# STM32_LineFlow.net
KiCad netlist of a schematic drawn in Altium Designer
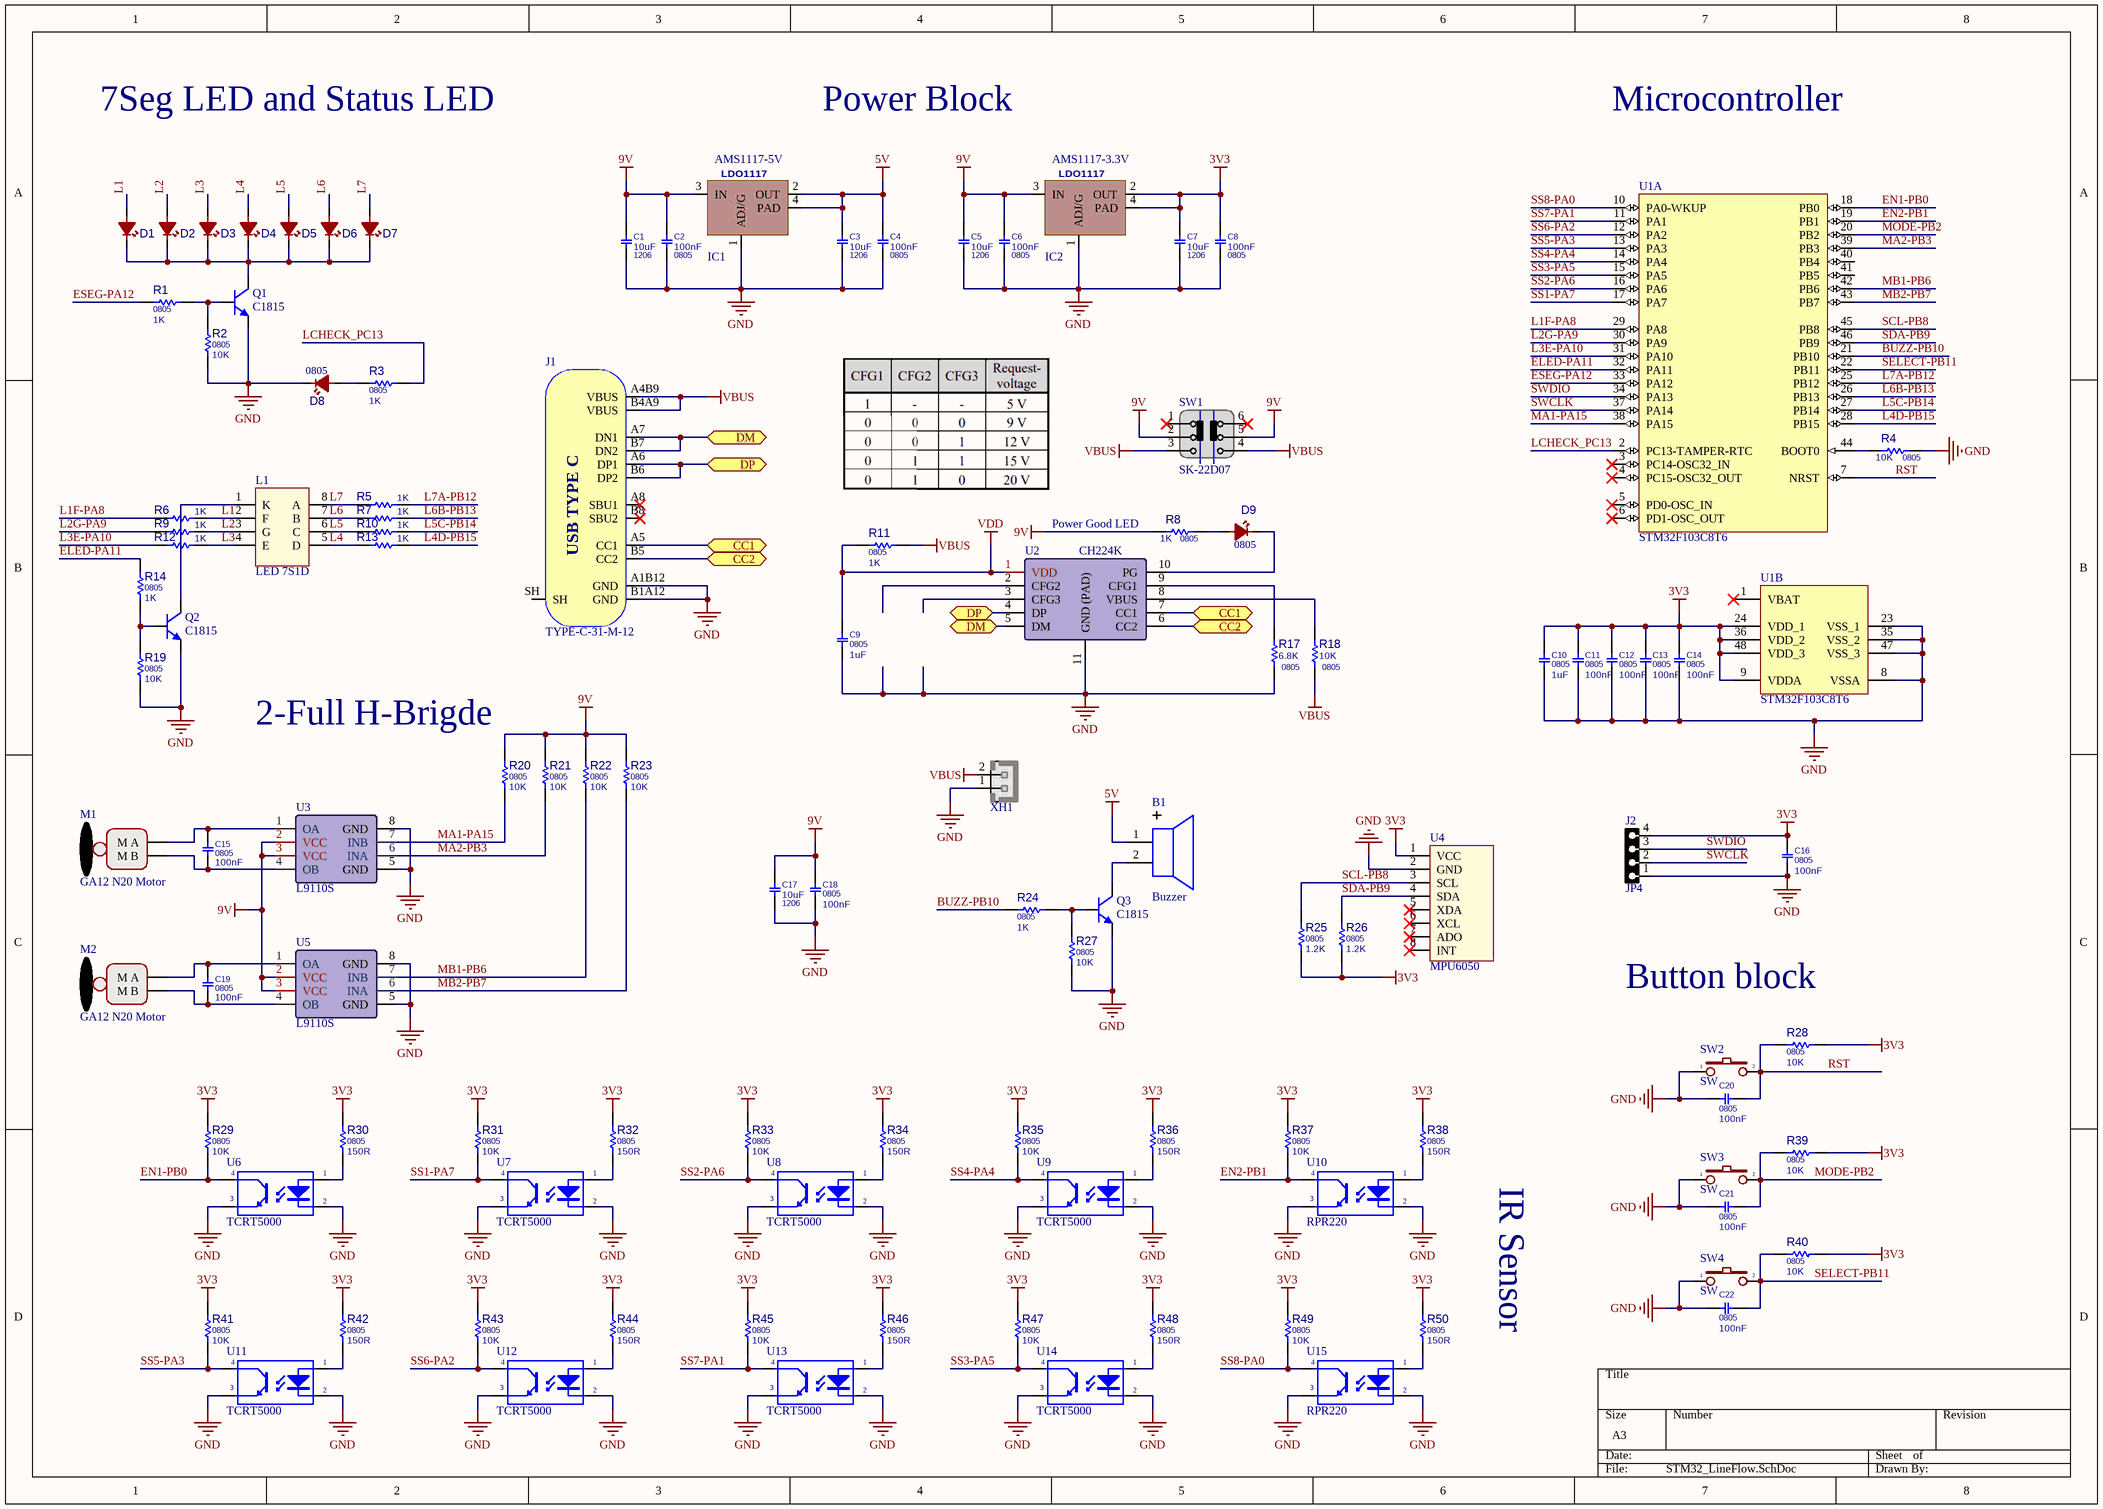
[diagram p0: STM32_LineFlow.SchDoc]

(export (version "E")
  (design (tool "Eeschema 10.0.6"))
  (components
    (comp (ref "B1") (value "Buzzer") (footprint "Buzzer") (libsource (lib "IoT - Copy") (part "Buzzer")))
    (comp (ref "C1")
      (value "1206")
      (footprint "cap_1206")
      (description "CAP SMD")
      (fields (field (name "MANF_P#") "MANF_PART#") (field (name "ALTIUM_VALUE") "10uF"))
      (libsource (lib "IoT") (part "CAP SMD"))
    )
    (comp (ref "C2")
      (value "0805")
      (footprint "cap_0805")
      (description "CAP SMD")
      (fields (field (name "MANF_P#") "MANF_PART#") (field (name "ALTIUM_VALUE") "100nF"))
      (libsource (lib "IoT") (part "CAP SMD"))
    )
    (comp (ref "C3")
      (value "1206")
      (footprint "cap_1206")
      (description "CAP SMD")
      (fields (field (name "MANF_P#") "MANF_PART#") (field (name "ALTIUM_VALUE") "10uF"))
      (libsource (lib "IoT") (part "CAP SMD"))
    )
    (comp (ref "C4")
      (value "0805")
      (footprint "cap_0805")
      (description "CAP SMD")
      (fields (field (name "MANF_P#") "MANF_PART#") (field (name "ALTIUM_VALUE") "100nF"))
      (libsource (lib "IoT") (part "CAP SMD"))
    )
    (comp (ref "C5")
      (value "1206")
      (footprint "cap_1206")
      (description "CAP SMD")
      (fields (field (name "MANF_P#") "MANF_PART#") (field (name "ALTIUM_VALUE") "10uF"))
      (libsource (lib "IoT") (part "CAP SMD"))
    )
    (comp (ref "C6")
      (value "0805")
      (footprint "cap_0805")
      (description "CAP SMD")
      (fields (field (name "MANF_P#") "MANF_PART#") (field (name "ALTIUM_VALUE") "100nF"))
      (libsource (lib "IoT") (part "CAP SMD"))
    )
    (comp (ref "C7")
      (value "1206")
      (footprint "cap_1206")
      (description "CAP SMD")
      (fields (field (name "MANF_P#") "MANF_PART#") (field (name "ALTIUM_VALUE") "10uF"))
      (libsource (lib "IoT") (part "CAP SMD"))
    )
    (comp (ref "C8")
      (value "0805")
      (footprint "cap_0805")
      (description "CAP SMD")
      (fields (field (name "MANF_P#") "MANF_PART#") (field (name "ALTIUM_VALUE") "100nF"))
      (libsource (lib "IoT") (part "CAP SMD"))
    )
    (comp (ref "C9")
      (value "0805")
      (footprint "cap_0805")
      (description "CAP SMD")
      (fields (field (name "MANF_P#") "MANF_PART#") (field (name "ALTIUM_VALUE") "1uF"))
      (libsource (lib "IoT - Copy") (part "CAP SMD"))
    )
    (comp (ref "C10")
      (value "0805")
      (footprint "cap_0805")
      (description "CAP SMD")
      (fields (field (name "MANF_P#") "MANF_PART#") (field (name "ALTIUM_VALUE") "1uF"))
      (libsource (lib "IoT - Copy") (part "CAP SMD"))
    )
    (comp (ref "C11")
      (value "0805")
      (footprint "cap_0805")
      (description "CAP SMD")
      (fields (field (name "MANF_P#") "MANF_PART#") (field (name "ALTIUM_VALUE") "100nF"))
      (libsource (lib "IoT - Copy") (part "CAP SMD"))
    )
    (comp (ref "C12")
      (value "0805")
      (footprint "cap_0805")
      (description "CAP SMD")
      (fields (field (name "MANF_P#") "MANF_PART#") (field (name "ALTIUM_VALUE") "100nF"))
      (libsource (lib "IoT - Copy") (part "CAP SMD"))
    )
    (comp (ref "C13")
      (value "0805")
      (footprint "cap_0805")
      (description "CAP SMD")
      (fields (field (name "MANF_P#") "MANF_PART#") (field (name "ALTIUM_VALUE") "100nF"))
      (libsource (lib "IoT - Copy") (part "CAP SMD"))
    )
    (comp (ref "C14")
      (value "0805")
      (footprint "cap_0805")
      (description "CAP SMD")
      (fields (field (name "MANF_P#") "MANF_PART#") (field (name "ALTIUM_VALUE") "100nF"))
      (libsource (lib "IoT - Copy") (part "CAP SMD"))
    )
    (comp (ref "C15")
      (value "0805")
      (footprint "cap_0805")
      (description "CAP SMD")
      (fields (field (name "MANF_P#") "MANF_PART#") (field (name "ALTIUM_VALUE") "100nF"))
      (libsource (lib "IoT - Copy") (part "CAP SMD"))
    )
    (comp (ref "C16")
      (value "0805")
      (footprint "cap_0805")
      (description "CAP SMD")
      (fields (field (name "MANF_P#") "MANF_PART#") (field (name "ALTIUM_VALUE") "100nF"))
      (libsource (lib "IoT - Copy") (part "CAP SMD"))
    )
    (comp (ref "C17")
      (value "1206")
      (footprint "cap_1206")
      (description "CAP SMD")
      (fields (field (name "MANF_P#") "MANF_PART#") (field (name "ALTIUM_VALUE") "10uF"))
      (libsource (lib "IoT") (part "CAP SMD"))
    )
    (comp (ref "C18")
      (value "0805")
      (footprint "cap_0805")
      (description "CAP SMD")
      (fields (field (name "MANF_P#") "MANF_PART#") (field (name "ALTIUM_VALUE") "100nF"))
      (libsource (lib "IoT - Copy") (part "CAP SMD"))
    )
    (comp (ref "C19")
      (value "0805")
      (footprint "cap_0805")
      (description "CAP SMD")
      (fields (field (name "MANF_P#") "MANF_PART#") (field (name "ALTIUM_VALUE") "100nF"))
      (libsource (lib "IoT - Copy") (part "CAP SMD"))
    )
    (comp (ref "C20")
      (value "0805")
      (footprint "cap_0805")
      (description "CAP SMD")
      (fields (field (name "MANF_P#") "MANF_PART#") (field (name "ALTIUM_VALUE") "100nF"))
      (libsource (lib "IoT - Copy") (part "CAP SMD"))
    )
    (comp (ref "C21")
      (value "0805")
      (footprint "cap_0805")
      (description "CAP SMD")
      (fields (field (name "MANF_P#") "MANF_PART#") (field (name "ALTIUM_VALUE") "100nF"))
      (libsource (lib "IoT - Copy") (part "CAP SMD"))
    )
    (comp (ref "C22")
      (value "0805")
      (footprint "cap_0805")
      (description "CAP SMD")
      (fields (field (name "MANF_P#") "MANF_PART#") (field (name "ALTIUM_VALUE") "100nF"))
      (libsource (lib "IoT - Copy") (part "CAP SMD"))
    )
    (comp (ref "D1")
      (value "0805")
      (footprint "LED0805RED")
      (description "LED Red SMD")
      (fields (field (name "MANF") "MANF") (field (name "MANF_P#") "MANF_PART#"))
      (libsource (lib "IoT - Copy") (part "LED Red SMD"))
    )
    (comp (ref "D2")
      (value "0805")
      (footprint "LED0805RED")
      (description "LED Red SMD")
      (fields (field (name "MANF") "MANF") (field (name "MANF_P#") "MANF_PART#"))
      (libsource (lib "IoT - Copy") (part "LED Red SMD"))
    )
    (comp (ref "D3")
      (value "0805")
      (footprint "LED0805RED")
      (description "LED Red SMD")
      (fields (field (name "MANF") "MANF") (field (name "MANF_P#") "MANF_PART#"))
      (libsource (lib "IoT - Copy") (part "LED Red SMD"))
    )
    (comp (ref "D4")
      (value "0805")
      (footprint "LED0805RED")
      (description "LED Red SMD")
      (fields (field (name "MANF") "MANF") (field (name "MANF_P#") "MANF_PART#"))
      (libsource (lib "IoT - Copy") (part "LED Red SMD"))
    )
    (comp (ref "D5")
      (value "0805")
      (footprint "LED0805RED")
      (description "LED Red SMD")
      (fields (field (name "MANF") "MANF") (field (name "MANF_P#") "MANF_PART#"))
      (libsource (lib "IoT - Copy") (part "LED Red SMD"))
    )
    (comp (ref "D6")
      (value "0805")
      (footprint "LED0805RED")
      (description "LED Red SMD")
      (fields (field (name "MANF") "MANF") (field (name "MANF_P#") "MANF_PART#"))
      (libsource (lib "IoT - Copy") (part "LED Red SMD"))
    )
    (comp (ref "D7")
      (value "0805")
      (footprint "LED0805RED")
      (description "LED Red SMD")
      (fields (field (name "MANF") "MANF") (field (name "MANF_P#") "MANF_PART#"))
      (libsource (lib "IoT - Copy") (part "LED Red SMD"))
    )
    (comp (ref "D8")
      (value "0805")
      (footprint "LED0805RED")
      (description "LED Red SMD")
      (fields (field (name "MANF") "MANF") (field (name "MANF_P#") "MANF_PART#"))
      (libsource (lib "IoT - Copy") (part "LED Red SMD"))
    )
    (comp (ref "D9")
      (value "0805")
      (footprint "LED0805RED")
      (description "LED Red SMD")
      (fields (field (name "MANF") "MANF") (field (name "MANF_P#") "MANF_PART#"))
      (libsource (lib "IoT - Copy") (part "LED Red SMD"))
    )
    (comp (ref "IC1")
      (value "AMS1117-5V")
      (footprint "SOT223")
      (description "LDO 1117 Available in 1.8V, 2.5V, 2.85V, 3.3V, 5V, and  Adjustable Versions")
      (libsource (lib "IoT") (part "LDO 1117"))
    )
    (comp (ref "IC2")
      (value "AMS1117-3.3V")
      (footprint "SOT223")
      (description "LDO 1117 Available in 1.8V, 2.5V, 2.85V, 3.3V, 5V, and  Adjustable Versions")
      (libsource (lib "IoT") (part "LDO 1117"))
    )
    (comp (ref "J1")
      (value "TYPE-C-31-M-12")
      (footprint "TYPE-C-31-M-12")
      (description "USB Type C Connector Horizontal SMT")
      (fields (field (name "MANUFACTURER") "Koren Hroparts"))
      (libsource (lib "IoT - Copy") (part "TYPE-C-31-M-12"))
    )
    (comp (ref "J2") (value "JP4") (footprint "JP_4PIN") (libsource (lib "IoT - Copy") (part "JP4")))
    (comp (ref "L1")
      (value "LED 7S1D")
      (footprint "LED 7S1D 0.28\"")
      (libsource (lib "IoT - Copy") (part "LED 7S1D"))
    )
    (comp (ref "M1")
      (value "GA12 N20 Motor")
      (footprint "Motor GA-12 Type3")
      (description "GA12 N20 Metal Gear Motor")
      (libsource (lib "IoT - Copy") (part "GA12 N20 Motor"))
    )
    (comp (ref "M2")
      (value "GA12 N20 Motor")
      (footprint "Motor GA-12 Type2")
      (description "GA12 N20 Metal Gear Motor")
      (libsource (lib "IoT - Copy") (part "GA12 N20 Motor"))
    )
    (comp (ref "Q1")
      (value "C1815")
      (footprint "2SC1815-HF")
      (description "BJT C1815 Trans NPN 50V 150mA TO-92")
      (libsource (lib "IoT - Copy") (part "BJT 2SC1815"))
    )
    (comp (ref "Q2")
      (value "C1815")
      (footprint "2SC1815-HF")
      (description "BJT C1815 Trans NPN 50V 150mA TO-92")
      (libsource (lib "IoT - Copy") (part "BJT 2SC1815"))
    )
    (comp (ref "Q3")
      (value "C1815")
      (footprint "2SC1815-HF")
      (description "BJT C1815 Trans NPN 50V 150mA TO-92")
      (libsource (lib "IoT - Copy") (part "BJT 2SC1815"))
    )
    (comp (ref "R1")
      (value "0805")
      (footprint "R0805")
      (description "RES SMD")
      (fields
        (field (name "MANF_P#") "WSLP0805R0100FEA")
        (field (name "MANF") "VISHAY")
        (field (name "ALTIUM_VALUE") "1K")
      )
      (libsource (lib "IoT - Copy") (part "RES SMD"))
    )
    (comp (ref "R2")
      (value "0805")
      (footprint "R0805")
      (description "RES SMD")
      (fields
        (field (name "MANF_P#") "WSLP0805R0100FEA")
        (field (name "MANF") "VISHAY")
        (field (name "ALTIUM_VALUE") "10K")
      )
      (libsource (lib "IoT - Copy") (part "RES SMD"))
    )
    (comp (ref "R3")
      (value "0805")
      (footprint "R0805")
      (description "RES SMD")
      (fields
        (field (name "MANF_P#") "WSLP0805R0100FEA")
        (field (name "MANF") "VISHAY")
        (field (name "ALTIUM_VALUE") "1K")
      )
      (libsource (lib "IoT - Copy") (part "RES SMD"))
    )
    (comp (ref "R4")
      (value "0805")
      (footprint "R0805")
      (description "RES SMD")
      (fields
        (field (name "MANF_P#") "WSLP0805R0100FEA")
        (field (name "MANF") "VISHAY")
        (field (name "ALTIUM_VALUE") "10K")
      )
      (libsource (lib "IoT - Copy") (part "RES SMD"))
    )
    (comp (ref "R5")
      (value "1K")
      (footprint "R0805")
      (description "RES SMD")
      (fields (field (name "MANF_P#") "WSLP0805R0100FEA") (field (name "MANF") "VISHAY"))
      (libsource (lib "IoT - Copy") (part "RES SMD"))
    )
    (comp (ref "R6")
      (value "1K")
      (footprint "R0805")
      (description "RES SMD")
      (fields (field (name "MANF_P#") "WSLP0805R0100FEA") (field (name "MANF") "VISHAY"))
      (libsource (lib "IoT - Copy") (part "RES SMD"))
    )
    (comp (ref "R7")
      (value "1K")
      (footprint "R0805")
      (description "RES SMD")
      (fields (field (name "MANF_P#") "WSLP0805R0100FEA") (field (name "MANF") "VISHAY"))
      (libsource (lib "IoT - Copy") (part "RES SMD"))
    )
    (comp (ref "R8")
      (value "0805")
      (footprint "R0805")
      (description "RES SMD")
      (fields
        (field (name "MANF_P#") "WSLP0805R0100FEA")
        (field (name "MANF") "VISHAY")
        (field (name "ALTIUM_VALUE") "1K")
      )
      (libsource (lib "IoT - Copy") (part "RES SMD"))
    )
    (comp (ref "R9")
      (value "1K")
      (footprint "R0805")
      (description "RES SMD")
      (fields (field (name "MANF_P#") "WSLP0805R0100FEA") (field (name "MANF") "VISHAY"))
      (libsource (lib "IoT - Copy") (part "RES SMD"))
    )
    (comp (ref "R10")
      (value "1K")
      (footprint "R0805")
      (description "RES SMD")
      (fields (field (name "MANF_P#") "WSLP0805R0100FEA") (field (name "MANF") "VISHAY"))
      (libsource (lib "IoT - Copy") (part "RES SMD"))
    )
    (comp (ref "R11")
      (value "0805")
      (footprint "R0805")
      (description "RES SMD")
      (fields
        (field (name "MANF_P#") "WSLP0805R0100FEA")
        (field (name "MANF") "VISHAY")
        (field (name "ALTIUM_VALUE") "1K")
      )
      (libsource (lib "IoT - Copy") (part "RES SMD"))
    )
    (comp (ref "R12")
      (value "1K")
      (footprint "R0805")
      (description "RES SMD")
      (fields (field (name "MANF_P#") "WSLP0805R0100FEA") (field (name "MANF") "VISHAY"))
      (libsource (lib "IoT - Copy") (part "RES SMD"))
    )
    (comp (ref "R13")
      (value "1K")
      (footprint "R0805")
      (description "RES SMD")
      (fields (field (name "MANF_P#") "WSLP0805R0100FEA") (field (name "MANF") "VISHAY"))
      (libsource (lib "IoT - Copy") (part "RES SMD"))
    )
    (comp (ref "R14")
      (value "0805")
      (footprint "R0805")
      (description "RES SMD")
      (fields
        (field (name "MANF_P#") "WSLP0805R0100FEA")
        (field (name "MANF") "VISHAY")
        (field (name "ALTIUM_VALUE") "1K")
      )
      (libsource (lib "IoT - Copy") (part "RES SMD"))
    )
    (comp (ref "R17")
      (value "0805")
      (footprint "R0805")
      (description "RES SMD")
      (fields
        (field (name "MANF_P#") "WSLP0805R0100FEA")
        (field (name "MANF") "VISHAY")
        (field (name "ALTIUM_VALUE") "6.8K")
      )
      (libsource (lib "IoT - Copy") (part "RES SMD"))
    )
    (comp (ref "R18")
      (value "0805")
      (footprint "R0805")
      (description "RES SMD")
      (fields
        (field (name "MANF_P#") "WSLP0805R0100FEA")
        (field (name "MANF") "VISHAY")
        (field (name "ALTIUM_VALUE") "10K")
      )
      (libsource (lib "IoT - Copy") (part "RES SMD"))
    )
    (comp (ref "R19")
      (value "0805")
      (footprint "R0805")
      (description "RES SMD")
      (fields
        (field (name "MANF_P#") "WSLP0805R0100FEA")
        (field (name "MANF") "VISHAY")
        (field (name "ALTIUM_VALUE") "10K")
      )
      (libsource (lib "IoT - Copy") (part "RES SMD"))
    )
    (comp (ref "R20")
      (value "0805")
      (footprint "R0805")
      (description "RES SMD")
      (fields
        (field (name "MANF_P#") "WSLP0805R0100FEA")
        (field (name "MANF") "VISHAY")
        (field (name "ALTIUM_VALUE") "10K")
      )
      (libsource (lib "IoT - Copy") (part "RES SMD"))
    )
    (comp (ref "R21")
      (value "0805")
      (footprint "R0805")
      (description "RES SMD")
      (fields
        (field (name "MANF_P#") "WSLP0805R0100FEA")
        (field (name "MANF") "VISHAY")
        (field (name "ALTIUM_VALUE") "10K")
      )
      (libsource (lib "IoT - Copy") (part "RES SMD"))
    )
    (comp (ref "R22")
      (value "0805")
      (footprint "R0805")
      (description "RES SMD")
      (fields
        (field (name "MANF_P#") "WSLP0805R0100FEA")
        (field (name "MANF") "VISHAY")
        (field (name "ALTIUM_VALUE") "10K")
      )
      (libsource (lib "IoT - Copy") (part "RES SMD"))
    )
    (comp (ref "R23")
      (value "0805")
      (footprint "R0805")
      (description "RES SMD")
      (fields
        (field (name "MANF_P#") "WSLP0805R0100FEA")
        (field (name "MANF") "VISHAY")
        (field (name "ALTIUM_VALUE") "10K")
      )
      (libsource (lib "IoT - Copy") (part "RES SMD"))
    )
    (comp (ref "R24")
      (value "0805")
      (footprint "R0805")
      (description "RES SMD")
      (fields
        (field (name "MANF_P#") "WSLP0805R0100FEA")
        (field (name "MANF") "VISHAY")
        (field (name "ALTIUM_VALUE") "1K")
      )
      (libsource (lib "IoT - Copy") (part "RES SMD"))
    )
    (comp (ref "R25")
      (value "0805")
      (footprint "R0805")
      (description "RES SMD")
      (fields
        (field (name "MANF_P#") "WSLP0805R0100FEA")
        (field (name "MANF") "VISHAY")
        (field (name "ALTIUM_VALUE") "1.2K")
      )
      (libsource (lib "IoT - Copy") (part "RES SMD"))
    )
    (comp (ref "R26")
      (value "0805")
      (footprint "R0805")
      (description "RES SMD")
      (fields
        (field (name "MANF_P#") "WSLP0805R0100FEA")
        (field (name "MANF") "VISHAY")
        (field (name "ALTIUM_VALUE") "1.2K")
      )
      (libsource (lib "IoT - Copy") (part "RES SMD"))
    )
    (comp (ref "R27")
      (value "0805")
      (footprint "R0805")
      (description "RES SMD")
      (fields
        (field (name "MANF_P#") "WSLP0805R0100FEA")
        (field (name "MANF") "VISHAY")
        (field (name "ALTIUM_VALUE") "10K")
      )
      (libsource (lib "IoT - Copy") (part "RES SMD"))
    )
    (comp (ref "R28")
      (value "0805")
      (footprint "R0805")
      (description "RES SMD")
      (fields
        (field (name "MANF_P#") "WSLP0805R0100FEA")
        (field (name "MANF") "VISHAY")
        (field (name "ALTIUM_VALUE") "10K")
      )
      (libsource (lib "IoT - Copy") (part "RES SMD"))
    )
    (comp (ref "R29")
      (value "0805")
      (footprint "R0805")
      (description "RES SMD")
      (fields
        (field (name "MANF_P#") "WSLP0805R0100FEA")
        (field (name "MANF") "VISHAY")
        (field (name "ALTIUM_VALUE") "10K")
      )
      (libsource (lib "IoT - Copy") (part "RES SMD"))
    )
    (comp (ref "R30")
      (value "0805")
      (footprint "R0805")
      (description "RES SMD")
      (fields
        (field (name "MANF_P#") "WSLP0805R0100FEA")
        (field (name "MANF") "VISHAY")
        (field (name "ALTIUM_VALUE") "150R")
      )
      (libsource (lib "IoT - Copy") (part "RES SMD"))
    )
    (comp (ref "R31")
      (value "0805")
      (footprint "R0805")
      (description "RES SMD")
      (fields
        (field (name "MANF_P#") "WSLP0805R0100FEA")
        (field (name "MANF") "VISHAY")
        (field (name "ALTIUM_VALUE") "10K")
      )
      (libsource (lib "IoT - Copy") (part "RES SMD"))
    )
    (comp (ref "R32")
      (value "0805")
      (footprint "R0805")
      (description "RES SMD")
      (fields
        (field (name "MANF_P#") "WSLP0805R0100FEA")
        (field (name "MANF") "VISHAY")
        (field (name "ALTIUM_VALUE") "150R")
      )
      (libsource (lib "IoT - Copy") (part "RES SMD"))
    )
    (comp (ref "R33")
      (value "0805")
      (footprint "R0805")
      (description "RES SMD")
      (fields
        (field (name "MANF_P#") "WSLP0805R0100FEA")
        (field (name "MANF") "VISHAY")
        (field (name "ALTIUM_VALUE") "10K")
      )
      (libsource (lib "IoT - Copy") (part "RES SMD"))
    )
    (comp (ref "R34")
      (value "0805")
      (footprint "R0805")
      (description "RES SMD")
      (fields
        (field (name "MANF_P#") "WSLP0805R0100FEA")
        (field (name "MANF") "VISHAY")
        (field (name "ALTIUM_VALUE") "150R")
      )
      (libsource (lib "IoT - Copy") (part "RES SMD"))
    )
    (comp (ref "R35")
      (value "0805")
      (footprint "R0805")
      (description "RES SMD")
      (fields
        (field (name "MANF_P#") "WSLP0805R0100FEA")
        (field (name "MANF") "VISHAY")
        (field (name "ALTIUM_VALUE") "10K")
      )
      (libsource (lib "IoT - Copy") (part "RES SMD"))
    )
    (comp (ref "R36")
      (value "0805")
      (footprint "R0805")
      (description "RES SMD")
      (fields
        (field (name "MANF_P#") "WSLP0805R0100FEA")
        (field (name "MANF") "VISHAY")
        (field (name "ALTIUM_VALUE") "150R")
      )
      (libsource (lib "IoT - Copy") (part "RES SMD"))
    )
    (comp (ref "R37")
      (value "0805")
      (footprint "R0805")
      (description "RES SMD")
      (fields
        (field (name "MANF_P#") "WSLP0805R0100FEA")
        (field (name "MANF") "VISHAY")
        (field (name "ALTIUM_VALUE") "10K")
      )
      (libsource (lib "IoT - Copy") (part "RES SMD"))
    )
    (comp (ref "R38")
      (value "0805")
      (footprint "R0805")
      (description "RES SMD")
      (fields
        (field (name "MANF_P#") "WSLP0805R0100FEA")
        (field (name "MANF") "VISHAY")
        (field (name "ALTIUM_VALUE") "150R")
      )
      (libsource (lib "IoT - Copy") (part "RES SMD"))
    )
    (comp (ref "R39")
      (value "0805")
      (footprint "R0805")
      (description "RES SMD")
      (fields
        (field (name "MANF_P#") "WSLP0805R0100FEA")
        (field (name "MANF") "VISHAY")
        (field (name "ALTIUM_VALUE") "10K")
      )
      (libsource (lib "IoT - Copy") (part "RES SMD"))
    )
    (comp (ref "R40")
      (value "0805")
      (footprint "R0805")
      (description "RES SMD")
      (fields
        (field (name "MANF_P#") "WSLP0805R0100FEA")
        (field (name "MANF") "VISHAY")
        (field (name "ALTIUM_VALUE") "10K")
      )
      (libsource (lib "IoT - Copy") (part "RES SMD"))
    )
    (comp (ref "R41")
      (value "0805")
      (footprint "R0805")
      (description "RES SMD")
      (fields
        (field (name "MANF_P#") "WSLP0805R0100FEA")
        (field (name "MANF") "VISHAY")
        (field (name "ALTIUM_VALUE") "10K")
      )
      (libsource (lib "IoT - Copy") (part "RES SMD"))
    )
    (comp (ref "R42")
      (value "0805")
      (footprint "R0805")
      (description "RES SMD")
      (fields
        (field (name "MANF_P#") "WSLP0805R0100FEA")
        (field (name "MANF") "VISHAY")
        (field (name "ALTIUM_VALUE") "150R")
      )
      (libsource (lib "IoT - Copy") (part "RES SMD"))
    )
    (comp (ref "R43")
      (value "0805")
      (footprint "R0805")
      (description "RES SMD")
      (fields
        (field (name "MANF_P#") "WSLP0805R0100FEA")
        (field (name "MANF") "VISHAY")
        (field (name "ALTIUM_VALUE") "10K")
      )
      (libsource (lib "IoT - Copy") (part "RES SMD"))
    )
    (comp (ref "R44")
      (value "0805")
      (footprint "R0805")
      (description "RES SMD")
      (fields
        (field (name "MANF_P#") "WSLP0805R0100FEA")
        (field (name "MANF") "VISHAY")
        (field (name "ALTIUM_VALUE") "150R")
      )
      (libsource (lib "IoT - Copy") (part "RES SMD"))
    )
    (comp (ref "R45")
      (value "0805")
      (footprint "R0805")
      (description "RES SMD")
      (fields
        (field (name "MANF_P#") "WSLP0805R0100FEA")
        (field (name "MANF") "VISHAY")
        (field (name "ALTIUM_VALUE") "10K")
      )
      (libsource (lib "IoT - Copy") (part "RES SMD"))
    )
    (comp (ref "R46")
      (value "0805")
      (footprint "R0805")
      (description "RES SMD")
      (fields
        (field (name "MANF_P#") "WSLP0805R0100FEA")
        (field (name "MANF") "VISHAY")
        (field (name "ALTIUM_VALUE") "150R")
      )
      (libsource (lib "IoT - Copy") (part "RES SMD"))
    )
    (comp (ref "R47")
      (value "0805")
      (footprint "R0805")
      (description "RES SMD")
      (fields
        (field (name "MANF_P#") "WSLP0805R0100FEA")
        (field (name "MANF") "VISHAY")
        (field (name "ALTIUM_VALUE") "10K")
      )
      (libsource (lib "IoT - Copy") (part "RES SMD"))
    )
    (comp (ref "R48")
      (value "0805")
      (footprint "R0805")
      (description "RES SMD")
      (fields
        (field (name "MANF_P#") "WSLP0805R0100FEA")
        (field (name "MANF") "VISHAY")
        (field (name "ALTIUM_VALUE") "150R")
      )
      (libsource (lib "IoT - Copy") (part "RES SMD"))
    )
    (comp (ref "R49")
      (value "0805")
      (footprint "R0805")
      (description "RES SMD")
      (fields
        (field (name "MANF_P#") "WSLP0805R0100FEA")
        (field (name "MANF") "VISHAY")
        (field (name "ALTIUM_VALUE") "10K")
      )
      (libsource (lib "IoT - Copy") (part "RES SMD"))
    )
    (comp (ref "R50")
      (value "0805")
      (footprint "R0805")
      (description "RES SMD")
      (fields
        (field (name "MANF_P#") "WSLP0805R0100FEA")
        (field (name "MANF") "VISHAY")
        (field (name "ALTIUM_VALUE") "150R")
      )
      (libsource (lib "IoT - Copy") (part "RES SMD"))
    )
    (comp (ref "SW1")
      (value "SK-22D07")
      (footprint "IoT - Copy:SK-22D07")
      (description "SW SK-22D07 Công Tắc Trượt 6 Chân Xuyên Lỗ ON-ON 2P2T 1A")
      (libsource (lib "IoT - Copy") (part "SW SK-22D07"))
    )
    (comp (ref "SW2")
      (value "SW")
      (footprint "SW-SMD")
      (description "Switch button 2 pin")
      (libsource (lib "IoT - Copy") (part "SW2"))
    )
    (comp (ref "SW3")
      (value "SW")
      (footprint "SW-SMD")
      (description "Switch button 2 pin")
      (libsource (lib "IoT - Copy") (part "SW2"))
    )
    (comp (ref "SW4")
      (value "SW")
      (footprint "SW-SMD")
      (description "Switch button 2 pin")
      (libsource (lib "IoT - Copy") (part "SW2"))
    )
    (comp (ref "U1")
      (value "STM32F103C8T6")
      (footprint "STM-LQFP48_N")
      (libsource (lib "IoT - Copy") (part "STM32F103C8T6AB"))
    )
    (comp (ref "U2")
      (value "CH224K")
      (footprint "ESOP-10 CHAY")
      (description "CH224K USB PD Decoy, USB Power Delivery Decoy")
      (libsource (lib "IoT - Copy") (part "CH224K"))
    )
    (comp (ref "U3")
      (value "L9110S")
      (footprint "SOIC-8")
      (description "L9110")
      (libsource (lib "IoT - Copy") (part "L9110"))
    )
    (comp (ref "U4")
      (value "MPU6050")
      (footprint "MPU-6050")
      (description "MPU6050 Module")
      (libsource (lib "IoT - Copy") (part "MPU6050"))
    )
    (comp (ref "U5")
      (value "L9110S")
      (footprint "SOIC-8")
      (description "L9110")
      (libsource (lib "IoT - Copy") (part "L9110"))
    )
    (comp (ref "U6")
      (value "TCRT5000")
      (footprint "TCRT5000")
      (description "TCRT5000 Cảm Biến Hồng Ngoại Phản Xạ")
      (libsource (lib "IoT - Copy") (part "TCRT5000"))
    )
    (comp (ref "U7")
      (value "TCRT5000")
      (footprint "TCRT5000")
      (description "TCRT5000 Cảm Biến Hồng Ngoại Phản Xạ")
      (libsource (lib "IoT - Copy") (part "TCRT5000"))
    )
    (comp (ref "U8")
      (value "TCRT5000")
      (footprint "TCRT5000")
      (description "TCRT5000 Cảm Biến Hồng Ngoại Phản Xạ")
      (libsource (lib "IoT - Copy") (part "TCRT5000"))
    )
    (comp (ref "U9")
      (value "TCRT5000")
      (footprint "TCRT5000")
      (description "TCRT5000 Cảm Biến Hồng Ngoại Phản Xạ")
      (libsource (lib "IoT - Copy") (part "TCRT5000"))
    )
    (comp (ref "U10") (value "RPR220") (footprint "RPR220") (libsource (lib "IoT - Copy") (part "RPR220")))
    (comp (ref "U11")
      (value "TCRT5000")
      (footprint "TCRT5000")
      (description "TCRT5000 Cảm Biến Hồng Ngoại Phản Xạ")
      (libsource (lib "IoT - Copy") (part "TCRT5000"))
    )
    (comp (ref "U12")
      (value "TCRT5000")
      (footprint "TCRT5000")
      (description "TCRT5000 Cảm Biến Hồng Ngoại Phản Xạ")
      (libsource (lib "IoT - Copy") (part "TCRT5000"))
    )
    (comp (ref "U13")
      (value "TCRT5000")
      (footprint "TCRT5000")
      (description "TCRT5000 Cảm Biến Hồng Ngoại Phản Xạ")
      (libsource (lib "IoT - Copy") (part "TCRT5000"))
    )
    (comp (ref "U14")
      (value "TCRT5000")
      (footprint "TCRT5000")
      (description "TCRT5000 Cảm Biến Hồng Ngoại Phản Xạ")
      (libsource (lib "IoT - Copy") (part "TCRT5000"))
    )
    (comp (ref "U15") (value "RPR220") (footprint "RPR220") (libsource (lib "IoT - Copy") (part "RPR220")))
    (comp (ref "XH1")
      (value "HHDR_2")
      (footprint "XH_2")
      (description "XH 2 JST-XH pitch: 2.5mm")
      (libsource (lib "IoT - Copy") (part "XH_2"))
    )
  )
  (nets
    (net (code "1") (name "/BUZZ-PB10") (class "Default")
      (node (ref "R24") (pin "1") (pinfunction "1_1") (pintype "passive"))
      (node (ref "U1") (pin "21") (pinfunction "PB10_21") (pintype "bidirectional"))
    )
    (net (code "2") (name "/CC1") (class "Default")
      (node (ref "J1") (pin "A5") (pinfunction "CC1_A5") (pintype "passive"))
      (node (ref "U2") (pin "7") (pinfunction "CC1_7") (pintype "passive"))
    )
    (net (code "3") (name "/CC2") (class "Default")
      (node (ref "J1") (pin "B5") (pinfunction "CC2_B5") (pintype "tri_state"))
      (node (ref "U2") (pin "6") (pinfunction "CC2_6") (pintype "passive"))
    )
    (net (code "4") (name "/DM") (class "Default")
      (node (ref "J1") (pin "A7") (pinfunction "DN1_A7") (pintype "open_collector"))
      (node (ref "J1") (pin "B7") (pinfunction "DN2_B7") (pintype "open_collector"))
      (node (ref "U2") (pin "5") (pinfunction "DM_5") (pintype "passive"))
    )
    (net (code "5") (name "/DP") (class "Default")
      (node (ref "J1") (pin "A6") (pinfunction "DP1_A6") (pintype "open_collector"))
      (node (ref "J1") (pin "B6") (pinfunction "DP2_B6") (pintype "open_collector"))
      (node (ref "U2") (pin "4") (pinfunction "DP_4") (pintype "passive"))
    )
    (net (code "6") (name "/ELED-PA11") (class "Default")
      (node (ref "R14") (pin "1") (pinfunction "1_1") (pintype "passive"))
      (node (ref "U1") (pin "32") (pinfunction "PA11_32") (pintype "bidirectional"))
    )
    (net (code "7") (name "/EN1-PB0") (class "Default")
      (node (ref "R29") (pin "1") (pinfunction "1_1") (pintype "passive"))
      (node (ref "U1") (pin "18") (pinfunction "PB0_18") (pintype "bidirectional"))
      (node (ref "U6") (pin "4") (pinfunction "C_4") (pintype "passive"))
    )
    (net (code "8") (name "/EN2-PB1") (class "Default")
      (node (ref "R37") (pin "1") (pinfunction "1_1") (pintype "passive"))
      (node (ref "U1") (pin "19") (pinfunction "PB1_19") (pintype "bidirectional"))
      (node (ref "U10") (pin "4") (pinfunction "C_4") (pintype "passive"))
    )
    (net (code "9") (name "/ESEG-PA12") (class "Default")
      (node (ref "R1") (pin "1") (pinfunction "1_1") (pintype "passive"))
      (node (ref "U1") (pin "33") (pinfunction "PA12_33") (pintype "bidirectional"))
    )
    (net (code "10") (name "/L1") (class "Default")
      (node (ref "D1") (pin "1") (pinfunction "A_1") (pintype "passive"))
      (node (ref "L1") (pin "2") (pinfunction "F_2") (pintype "passive"))
      (node (ref "R6") (pin "1") (pinfunction "1_1") (pintype "passive"))
    )
    (net (code "11") (name "/L1F-PA8") (class "Default")
      (node (ref "R6") (pin "2") (pinfunction "2_2") (pintype "passive"))
      (node (ref "U1") (pin "29") (pinfunction "PA8_29") (pintype "bidirectional"))
    )
    (net (code "12") (name "/L2") (class "Default")
      (node (ref "D2") (pin "1") (pinfunction "A_1") (pintype "passive"))
      (node (ref "L1") (pin "3") (pinfunction "G_3") (pintype "passive"))
      (node (ref "R9") (pin "1") (pinfunction "1_1") (pintype "passive"))
    )
    (net (code "13") (name "/L2G-PA9") (class "Default")
      (node (ref "R9") (pin "2") (pinfunction "2_2") (pintype "passive"))
      (node (ref "U1") (pin "30") (pinfunction "PA9_30") (pintype "bidirectional"))
    )
    (net (code "14") (name "/L3") (class "Default")
      (node (ref "D3") (pin "1") (pinfunction "A_1") (pintype "passive"))
      (node (ref "L1") (pin "4") (pinfunction "E_4") (pintype "passive"))
      (node (ref "R12") (pin "1") (pinfunction "1_1") (pintype "passive"))
    )
    (net (code "15") (name "/L3E-PA10") (class "Default")
      (node (ref "R12") (pin "2") (pinfunction "2_2") (pintype "passive"))
      (node (ref "U1") (pin "31") (pinfunction "PA10_31") (pintype "bidirectional"))
    )
    (net (code "16") (name "/L4") (class "Default")
      (node (ref "D4") (pin "1") (pinfunction "A_1") (pintype "passive"))
      (node (ref "L1") (pin "5") (pinfunction "D_5") (pintype "passive"))
      (node (ref "R13") (pin "2") (pinfunction "2_2") (pintype "passive"))
    )
    (net (code "17") (name "/L4D-PB15") (class "Default")
      (node (ref "R13") (pin "1") (pinfunction "1_1") (pintype "passive"))
      (node (ref "U1") (pin "28") (pinfunction "PB15_28") (pintype "bidirectional"))
    )
    (net (code "18") (name "/L5") (class "Default")
      (node (ref "D5") (pin "1") (pinfunction "A_1") (pintype "passive"))
      (node (ref "L1") (pin "6") (pinfunction "C_6") (pintype "passive"))
      (node (ref "R10") (pin "2") (pinfunction "2_2") (pintype "passive"))
    )
    (net (code "19") (name "/L5C-PB14") (class "Default")
      (node (ref "R10") (pin "1") (pinfunction "1_1") (pintype "passive"))
      (node (ref "U1") (pin "27") (pinfunction "PB14_27") (pintype "bidirectional"))
    )
    (net (code "20") (name "/L6") (class "Default")
      (node (ref "D6") (pin "1") (pinfunction "A_1") (pintype "passive"))
      (node (ref "L1") (pin "7") (pinfunction "B_7") (pintype "passive"))
      (node (ref "R7") (pin "2") (pinfunction "2_2") (pintype "passive"))
    )
    (net (code "21") (name "/L6B-PB13") (class "Default")
      (node (ref "R7") (pin "1") (pinfunction "1_1") (pintype "passive"))
      (node (ref "U1") (pin "26") (pinfunction "PB13_26") (pintype "bidirectional"))
    )
    (net (code "22") (name "/L7") (class "Default")
      (node (ref "D7") (pin "1") (pinfunction "A_1") (pintype "passive"))
      (node (ref "L1") (pin "8") (pinfunction "A_8") (pintype "passive"))
      (node (ref "R5") (pin "2") (pinfunction "2_2") (pintype "passive"))
    )
    (net (code "23") (name "/L7A-PB12") (class "Default")
      (node (ref "R5") (pin "1") (pinfunction "1_1") (pintype "passive"))
      (node (ref "U1") (pin "25") (pinfunction "PB12_25") (pintype "bidirectional"))
    )
    (net (code "24") (name "/LCHECK_PC13") (class "Default")
      (node (ref "R3") (pin "1") (pinfunction "1_1") (pintype "passive"))
      (node (ref "U1") (pin "2") (pinfunction "PC13-TAMPER-RTC_2") (pintype "bidirectional"))
    )
    (net (code "25") (name "/MA1-PA15") (class "Default")
      (node (ref "R20") (pin "1") (pinfunction "1_1") (pintype "passive"))
      (node (ref "U1") (pin "38") (pinfunction "PA15_38") (pintype "bidirectional"))
      (node (ref "U3") (pin "7") (pinfunction "INB_7") (pintype "passive"))
    )
    (net (code "26") (name "/MA2-PB3") (class "Default")
      (node (ref "R21") (pin "1") (pinfunction "1_1") (pintype "passive"))
      (node (ref "U1") (pin "39") (pinfunction "PB3_39") (pintype "bidirectional"))
      (node (ref "U3") (pin "6") (pinfunction "INA_6") (pintype "passive"))
    )
    (net (code "27") (name "/MB1-PB6") (class "Default")
      (node (ref "R22") (pin "1") (pinfunction "1_1") (pintype "passive"))
      (node (ref "U1") (pin "42") (pinfunction "PB6_42") (pintype "bidirectional"))
      (node (ref "U5") (pin "7") (pinfunction "INB_7") (pintype "passive"))
    )
    (net (code "28") (name "/MB2-PB7") (class "Default")
      (node (ref "R23") (pin "1") (pinfunction "1_1") (pintype "passive"))
      (node (ref "U1") (pin "43") (pinfunction "PB7_43") (pintype "bidirectional"))
      (node (ref "U5") (pin "6") (pinfunction "INA_6") (pintype "passive"))
    )
    (net (code "29") (name "/MODE-PB2") (class "Default")
      (node (ref "C21") (pin "1") (pinfunction "1_1") (pintype "passive"))
      (node (ref "R39") (pin "2") (pinfunction "2_2") (pintype "passive"))
      (node (ref "SW3") (pin "2") (pinfunction "2_2") (pintype "passive"))
      (node (ref "U1") (pin "20") (pinfunction "PB2_20") (pintype "bidirectional"))
    )
    (net (code "30") (name "/RST") (class "Default")
      (node (ref "C20") (pin "1") (pinfunction "1_1") (pintype "passive"))
      (node (ref "R28") (pin "2") (pinfunction "2_2") (pintype "passive"))
      (node (ref "SW2") (pin "2") (pinfunction "2_2") (pintype "passive"))
      (node (ref "U1") (pin "7") (pinfunction "NRST_7") (pintype "bidirectional"))
    )
    (net (code "31") (name "/SCL-PB8") (class "Default")
      (node (ref "R25") (pin "2") (pinfunction "2_2") (pintype "passive"))
      (node (ref "U1") (pin "45") (pinfunction "PB8_45") (pintype "bidirectional"))
      (node (ref "U4") (pin "3") (pinfunction "SCL_3") (pintype "passive"))
    )
    (net (code "32") (name "/SDA-PB9") (class "Default")
      (node (ref "R26") (pin "2") (pinfunction "2_2") (pintype "passive"))
      (node (ref "U1") (pin "46") (pinfunction "PB9_46") (pintype "bidirectional"))
      (node (ref "U4") (pin "4") (pinfunction "SDA_4") (pintype "passive"))
    )
    (net (code "33") (name "/SELECT-PB11") (class "Default")
      (node (ref "C22") (pin "1") (pinfunction "1_1") (pintype "passive"))
      (node (ref "R40") (pin "2") (pinfunction "2_2") (pintype "passive"))
      (node (ref "SW4") (pin "2") (pinfunction "2_2") (pintype "passive"))
      (node (ref "U1") (pin "22") (pinfunction "PB11_22") (pintype "bidirectional"))
    )
    (net (code "34") (name "/SS1-PA7") (class "Default")
      (node (ref "R31") (pin "1") (pinfunction "1_1") (pintype "passive"))
      (node (ref "U1") (pin "17") (pinfunction "PA7_17") (pintype "bidirectional"))
      (node (ref "U7") (pin "4") (pinfunction "C_4") (pintype "passive"))
    )
    (net (code "35") (name "/SS2-PA6") (class "Default")
      (node (ref "R33") (pin "1") (pinfunction "1_1") (pintype "passive"))
      (node (ref "U1") (pin "16") (pinfunction "PA6_16") (pintype "bidirectional"))
      (node (ref "U8") (pin "4") (pinfunction "C_4") (pintype "passive"))
    )
    (net (code "36") (name "/SS3-PA5") (class "Default")
      (node (ref "R47") (pin "1") (pinfunction "1_1") (pintype "passive"))
      (node (ref "U1") (pin "15") (pinfunction "PA5_15") (pintype "bidirectional"))
      (node (ref "U14") (pin "4") (pinfunction "C_4") (pintype "passive"))
    )
    (net (code "37") (name "/SS4-PA4") (class "Default")
      (node (ref "R35") (pin "1") (pinfunction "1_1") (pintype "passive"))
      (node (ref "U1") (pin "14") (pinfunction "PA4_14") (pintype "bidirectional"))
      (node (ref "U9") (pin "4") (pinfunction "C_4") (pintype "passive"))
    )
    (net (code "38") (name "/SS5-PA3") (class "Default")
      (node (ref "R41") (pin "1") (pinfunction "1_1") (pintype "passive"))
      (node (ref "U1") (pin "13") (pinfunction "PA3_13") (pintype "bidirectional"))
      (node (ref "U11") (pin "4") (pinfunction "C_4") (pintype "passive"))
    )
    (net (code "39") (name "/SS6-PA2") (class "Default")
      (node (ref "R43") (pin "1") (pinfunction "1_1") (pintype "passive"))
      (node (ref "U1") (pin "12") (pinfunction "PA2_12") (pintype "bidirectional"))
      (node (ref "U12") (pin "4") (pinfunction "C_4") (pintype "passive"))
    )
    (net (code "40") (name "/SS7-PA1") (class "Default")
      (node (ref "R45") (pin "1") (pinfunction "1_1") (pintype "passive"))
      (node (ref "U1") (pin "11") (pinfunction "PA1_11") (pintype "bidirectional"))
      (node (ref "U13") (pin "4") (pinfunction "C_4") (pintype "passive"))
    )
    (net (code "41") (name "/SS8-PA0") (class "Default")
      (node (ref "R49") (pin "1") (pinfunction "1_1") (pintype "passive"))
      (node (ref "U1") (pin "10") (pinfunction "PA0-WKUP_10") (pintype "bidirectional"))
      (node (ref "U15") (pin "4") (pinfunction "C_4") (pintype "passive"))
    )
    (net (code "42") (name "/SWCLK") (class "Default")
      (node (ref "J2") (pin "2") (pinfunction "2_2") (pintype "passive"))
      (node (ref "U1") (pin "37") (pinfunction "PA14_37") (pintype "bidirectional"))
    )
    (net (code "43") (name "/SWDIO") (class "Default")
      (node (ref "J2") (pin "3") (pinfunction "3_3") (pintype "passive"))
      (node (ref "U1") (pin "34") (pinfunction "PA13_34") (pintype "bidirectional"))
    )
    (net (code "44") (name "3V3") (class "Default")
      (node (ref "C10") (pin "2") (pinfunction "2_2") (pintype "passive"))
      (node (ref "C11") (pin "2") (pinfunction "2_2") (pintype "passive"))
      (node (ref "C12") (pin "2") (pinfunction "2_2") (pintype "passive"))
      (node (ref "C13") (pin "2") (pinfunction "2_2") (pintype "passive"))
      (node (ref "C14") (pin "2") (pinfunction "2_2") (pintype "passive"))
      (node (ref "C16") (pin "2") (pinfunction "2_2") (pintype "passive"))
      (node (ref "C7") (pin "2") (pinfunction "2_2") (pintype "passive"))
      (node (ref "C8") (pin "2") (pinfunction "2_2") (pintype "passive"))
      (node (ref "IC2") (pin "2") (pinfunction "OUT_2") (pintype "passive"))
      (node (ref "IC2") (pin "4") (pinfunction "PAD_4") (pintype "passive"))
      (node (ref "J2") (pin "4") (pinfunction "4_4") (pintype "passive"))
      (node (ref "R25") (pin "1") (pinfunction "1_1") (pintype "passive"))
      (node (ref "R26") (pin "1") (pinfunction "1_1") (pintype "passive"))
      (node (ref "R28") (pin "1") (pinfunction "1_1") (pintype "passive"))
      (node (ref "R29") (pin "2") (pinfunction "2_2") (pintype "passive"))
      (node (ref "R30") (pin "2") (pinfunction "2_2") (pintype "passive"))
      (node (ref "R31") (pin "2") (pinfunction "2_2") (pintype "passive"))
      (node (ref "R32") (pin "2") (pinfunction "2_2") (pintype "passive"))
      (node (ref "R33") (pin "2") (pinfunction "2_2") (pintype "passive"))
      (node (ref "R34") (pin "2") (pinfunction "2_2") (pintype "passive"))
      (node (ref "R35") (pin "2") (pinfunction "2_2") (pintype "passive"))
      (node (ref "R36") (pin "2") (pinfunction "2_2") (pintype "passive"))
      (node (ref "R37") (pin "2") (pinfunction "2_2") (pintype "passive"))
      (node (ref "R38") (pin "2") (pinfunction "2_2") (pintype "passive"))
      (node (ref "R39") (pin "1") (pinfunction "1_1") (pintype "passive"))
      (node (ref "R40") (pin "1") (pinfunction "1_1") (pintype "passive"))
      (node (ref "R41") (pin "2") (pinfunction "2_2") (pintype "passive"))
      (node (ref "R42") (pin "2") (pinfunction "2_2") (pintype "passive"))
      (node (ref "R43") (pin "2") (pinfunction "2_2") (pintype "passive"))
      (node (ref "R44") (pin "2") (pinfunction "2_2") (pintype "passive"))
      (node (ref "R45") (pin "2") (pinfunction "2_2") (pintype "passive"))
      (node (ref "R46") (pin "2") (pinfunction "2_2") (pintype "passive"))
      (node (ref "R47") (pin "2") (pinfunction "2_2") (pintype "passive"))
      (node (ref "R48") (pin "2") (pinfunction "2_2") (pintype "passive"))
      (node (ref "R49") (pin "2") (pinfunction "2_2") (pintype "passive"))
      (node (ref "R50") (pin "2") (pinfunction "2_2") (pintype "passive"))
      (node (ref "U1") (pin "24") (pinfunction "VDD_1_24") (pintype "power_in"))
      (node (ref "U1") (pin "36") (pinfunction "VDD_2_36") (pintype "power_in"))
      (node (ref "U1") (pin "48") (pinfunction "VDD_3_48") (pintype "power_in"))
      (node (ref "U1") (pin "9") (pinfunction "VDDA_9") (pintype "power_in"))
      (node (ref "U4") (pin "1") (pinfunction "VCC_1") (pintype "passive"))
    )
    (net (code "45") (name "5V") (class "Default")
      (node (ref "B1") (pin "1") (pinfunction "+_1") (pintype "passive"))
      (node (ref "C3") (pin "2") (pinfunction "2_2") (pintype "passive"))
      (node (ref "C4") (pin "2") (pinfunction "2_2") (pintype "passive"))
      (node (ref "IC1") (pin "2") (pinfunction "OUT_2") (pintype "passive"))
      (node (ref "IC1") (pin "4") (pinfunction "PAD_4") (pintype "passive"))
    )
    (net (code "46") (name "9V") (class "Default")
      (node (ref "C1") (pin "2") (pinfunction "2_2") (pintype "passive"))
      (node (ref "C17") (pin "2") (pinfunction "2_2") (pintype "passive"))
      (node (ref "C18") (pin "2") (pinfunction "2_2") (pintype "passive"))
      (node (ref "C2") (pin "2") (pinfunction "2_2") (pintype "passive"))
      (node (ref "C5") (pin "2") (pinfunction "2_2") (pintype "passive"))
      (node (ref "C6") (pin "2") (pinfunction "2_2") (pintype "passive"))
      (node (ref "IC1") (pin "3") (pinfunction "IN_3") (pintype "passive"))
      (node (ref "IC2") (pin "3") (pinfunction "IN_3") (pintype "passive"))
      (node (ref "R20") (pin "2") (pinfunction "2_2") (pintype "passive"))
      (node (ref "R21") (pin "2") (pinfunction "2_2") (pintype "passive"))
      (node (ref "R22") (pin "2") (pinfunction "2_2") (pintype "passive"))
      (node (ref "R23") (pin "2") (pinfunction "2_2") (pintype "passive"))
      (node (ref "R8") (pin "1") (pinfunction "1_1") (pintype "passive"))
      (node (ref "SW1") (pin "2") (pinfunction "P3_2") (pintype "passive"))
      (node (ref "SW1") (pin "5") (pinfunction "P3_5") (pintype "passive"))
      (node (ref "U3") (pin "2") (pinfunction "VCC_2") (pintype "passive"))
      (node (ref "U3") (pin "3") (pinfunction "VCC_3") (pintype "passive"))
      (node (ref "U5") (pin "2") (pinfunction "VCC_2") (pintype "passive"))
      (node (ref "U5") (pin "3") (pinfunction "VCC_3") (pintype "passive"))
    )
    (net (code "47") (name "GND") (class "Default")
      (node (ref "C1") (pin "1") (pinfunction "1_1") (pintype "passive"))
      (node (ref "C10") (pin "1") (pinfunction "1_1") (pintype "passive"))
      (node (ref "C11") (pin "1") (pinfunction "1_1") (pintype "passive"))
      (node (ref "C12") (pin "1") (pinfunction "1_1") (pintype "passive"))
      (node (ref "C13") (pin "1") (pinfunction "1_1") (pintype "passive"))
      (node (ref "C14") (pin "1") (pinfunction "1_1") (pintype "passive"))
      (node (ref "C16") (pin "1") (pinfunction "1_1") (pintype "passive"))
      (node (ref "C17") (pin "1") (pinfunction "1_1") (pintype "passive"))
      (node (ref "C18") (pin "1") (pinfunction "1_1") (pintype "passive"))
      (node (ref "C2") (pin "1") (pinfunction "1_1") (pintype "passive"))
      (node (ref "C20") (pin "2") (pinfunction "2_2") (pintype "passive"))
      (node (ref "C21") (pin "2") (pinfunction "2_2") (pintype "passive"))
      (node (ref "C22") (pin "2") (pinfunction "2_2") (pintype "passive"))
      (node (ref "C3") (pin "1") (pinfunction "1_1") (pintype "passive"))
      (node (ref "C4") (pin "1") (pinfunction "1_1") (pintype "passive"))
      (node (ref "C5") (pin "1") (pinfunction "1_1") (pintype "passive"))
      (node (ref "C6") (pin "1") (pinfunction "1_1") (pintype "passive"))
      (node (ref "C7") (pin "1") (pinfunction "1_1") (pintype "passive"))
      (node (ref "C8") (pin "1") (pinfunction "1_1") (pintype "passive"))
      (node (ref "C9") (pin "1") (pinfunction "1_1") (pintype "passive"))
      (node (ref "D8") (pin "2") (pinfunction "K_2") (pintype "passive"))
      (node (ref "IC1") (pin "1") (pinfunction "ADJ/G_1") (pintype "passive"))
      (node (ref "IC2") (pin "1") (pinfunction "ADJ/G_1") (pintype "passive"))
      (node (ref "J1") (pin "A1B12") (pinfunction "GND_A1B12") (pintype "power_in"))
      (node (ref "J1") (pin "B1A12") (pinfunction "GND_B1A12") (pintype "power_in"))
      (node (ref "J2") (pin "1") (pinfunction "1_1") (pintype "passive"))
      (node (ref "Q1") (pin "1") (pinfunction "E_1") (pintype "passive"))
      (node (ref "Q2") (pin "1") (pinfunction "E_1") (pintype "passive"))
      (node (ref "Q3") (pin "1") (pinfunction "E_1") (pintype "passive"))
      (node (ref "R17") (pin "1") (pinfunction "1_1") (pintype "passive"))
      (node (ref "R19") (pin "1") (pinfunction "1_1") (pintype "passive"))
      (node (ref "R2") (pin "1") (pinfunction "1_1") (pintype "passive"))
      (node (ref "R27") (pin "1") (pinfunction "1_1") (pintype "passive"))
      (node (ref "R4") (pin "1") (pinfunction "1_1") (pintype "passive"))
      (node (ref "SW2") (pin "1") (pinfunction "1_1") (pintype "passive"))
      (node (ref "SW3") (pin "1") (pinfunction "1_1") (pintype "passive"))
      (node (ref "SW4") (pin "1") (pinfunction "1_1") (pintype "passive"))
      (node (ref "U1") (pin "23") (pinfunction "VSS_1_23") (pintype "power_in"))
      (node (ref "U1") (pin "35") (pinfunction "VSS_2_35") (pintype "power_in"))
      (node (ref "U1") (pin "47") (pinfunction "VSS_3_47") (pintype "power_in"))
      (node (ref "U1") (pin "8") (pinfunction "VSSA_8") (pintype "power_in"))
      (node (ref "U10") (pin "2") (pinfunction "K_2") (pintype "passive"))
      (node (ref "U10") (pin "3") (pinfunction "E_3") (pintype "passive"))
      (node (ref "U11") (pin "2") (pinfunction "K_2") (pintype "passive"))
      (node (ref "U11") (pin "3") (pinfunction "E_3") (pintype "passive"))
      (node (ref "U12") (pin "2") (pinfunction "K_2") (pintype "passive"))
      (node (ref "U12") (pin "3") (pinfunction "E_3") (pintype "passive"))
      (node (ref "U13") (pin "2") (pinfunction "K_2") (pintype "passive"))
      (node (ref "U13") (pin "3") (pinfunction "E_3") (pintype "passive"))
      (node (ref "U14") (pin "2") (pinfunction "K_2") (pintype "passive"))
      (node (ref "U14") (pin "3") (pinfunction "E_3") (pintype "passive"))
      (node (ref "U15") (pin "2") (pinfunction "K_2") (pintype "passive"))
      (node (ref "U15") (pin "3") (pinfunction "E_3") (pintype "passive"))
      (node (ref "U2") (pin "11") (pinfunction "GND_(PAD)_11") (pintype "passive"))
      (node (ref "U3") (pin "5") (pinfunction "GND_5") (pintype "passive"))
      (node (ref "U3") (pin "8") (pinfunction "GND_8") (pintype "passive"))
      (node (ref "U4") (pin "2") (pinfunction "GND_2") (pintype "passive"))
      (node (ref "U5") (pin "5") (pinfunction "GND_5") (pintype "passive"))
      (node (ref "U5") (pin "8") (pinfunction "GND_8") (pintype "passive"))
      (node (ref "U6") (pin "2") (pinfunction "K_2") (pintype "passive"))
      (node (ref "U6") (pin "3") (pinfunction "E_3") (pintype "passive"))
      (node (ref "U7") (pin "2") (pinfunction "K_2") (pintype "passive"))
      (node (ref "U7") (pin "3") (pinfunction "E_3") (pintype "passive"))
      (node (ref "U8") (pin "2") (pinfunction "K_2") (pintype "passive"))
      (node (ref "U8") (pin "3") (pinfunction "E_3") (pintype "passive"))
      (node (ref "U9") (pin "2") (pinfunction "K_2") (pintype "passive"))
      (node (ref "U9") (pin "3") (pinfunction "E_3") (pintype "passive"))
      (node (ref "XH1") (pin "1") (pinfunction "1_1") (pintype "passive"))
    )
    (net (code "48") (name "Net-(B1--)") (class "Default")
      (node (ref "B1") (pin "2") (pinfunction "-_2") (pintype "passive"))
      (node (ref "Q3") (pin "2") (pinfunction "C_2") (pintype "passive"))
    )
    (net (code "49") (name "Net-(D1-K)") (class "Default")
      (node (ref "D1") (pin "2") (pinfunction "K_2") (pintype "passive"))
      (node (ref "D2") (pin "2") (pinfunction "K_2") (pintype "passive"))
      (node (ref "D3") (pin "2") (pinfunction "K_2") (pintype "passive"))
      (node (ref "D4") (pin "2") (pinfunction "K_2") (pintype "passive"))
      (node (ref "D5") (pin "2") (pinfunction "K_2") (pintype "passive"))
      (node (ref "D6") (pin "2") (pinfunction "K_2") (pintype "passive"))
      (node (ref "D7") (pin "2") (pinfunction "K_2") (pintype "passive"))
      (node (ref "Q1") (pin "2") (pinfunction "C_2") (pintype "passive"))
    )
    (net (code "50") (name "Net-(D8-A)") (class "Default")
      (node (ref "D8") (pin "1") (pinfunction "A_1") (pintype "passive"))
      (node (ref "R3") (pin "2") (pinfunction "2_2") (pintype "passive"))
    )
    (net (code "51") (name "Net-(D9-A)") (class "Default")
      (node (ref "D9") (pin "1") (pinfunction "A_1") (pintype "passive"))
      (node (ref "R8") (pin "2") (pinfunction "2_2") (pintype "passive"))
    )
    (net (code "52") (name "Net-(D9-K)") (class "Default")
      (node (ref "D9") (pin "2") (pinfunction "K_2") (pintype "passive"))
      (node (ref "U2") (pin "10") (pinfunction "PG_10") (pintype "passive"))
    )
    (net (code "53") (name "Net-(L1-K)") (class "Default")
      (node (ref "L1") (pin "1") (pinfunction "K_1") (pintype "passive"))
      (node (ref "Q2") (pin "2") (pinfunction "C_2") (pintype "passive"))
    )
    (net (code "54") (name "Net-(Q1-B)") (class "Default")
      (node (ref "Q1") (pin "3") (pinfunction "B_3") (pintype "passive"))
      (node (ref "R1") (pin "2") (pinfunction "2_2") (pintype "passive"))
      (node (ref "R2") (pin "2") (pinfunction "2_2") (pintype "passive"))
    )
    (net (code "55") (name "Net-(Q2-B)") (class "Default")
      (node (ref "Q2") (pin "3") (pinfunction "B_3") (pintype "passive"))
      (node (ref "R14") (pin "2") (pinfunction "2_2") (pintype "passive"))
      (node (ref "R19") (pin "2") (pinfunction "2_2") (pintype "passive"))
    )
    (net (code "56") (name "Net-(Q3-B)") (class "Default")
      (node (ref "Q3") (pin "3") (pinfunction "B_3") (pintype "passive"))
      (node (ref "R24") (pin "2") (pinfunction "2_2") (pintype "passive"))
      (node (ref "R27") (pin "2") (pinfunction "2_2") (pintype "passive"))
    )
    (net (code "57") (name "Net-(U1A-BOOT0)") (class "Default")
      (node (ref "R4") (pin "2") (pinfunction "2_2") (pintype "passive"))
      (node (ref "U1") (pin "44") (pinfunction "BOOT0_44") (pintype "input"))
    )
    (net (code "58") (name "Net-(U2-CFG1)") (class "Default")
      (node (ref "R17") (pin "2") (pinfunction "2_2") (pintype "passive"))
      (node (ref "U2") (pin "9") (pinfunction "CFG1_9") (pintype "passive"))
    )
    (net (code "59") (name "Net-(U2-VBUS)") (class "Default")
      (node (ref "R18") (pin "2") (pinfunction "2_2") (pintype "passive"))
      (node (ref "U2") (pin "8") (pinfunction "VBUS_8") (pintype "passive"))
    )
    (net (code "60") (name "Net-(U3-OA)") (class "Default")
      (node (ref "C15") (pin "2") (pinfunction "2_2") (pintype "passive"))
      (node (ref "M1") (pin "M_A") (pinfunction "M_A_M_A") (pintype "passive"))
      (node (ref "U3") (pin "1") (pinfunction "OA_1") (pintype "passive"))
    )
    (net (code "61") (name "Net-(U3-OB)") (class "Default")
      (node (ref "C15") (pin "1") (pinfunction "1_1") (pintype "passive"))
      (node (ref "M1") (pin "M_B") (pinfunction "M_B_M_B") (pintype "passive"))
      (node (ref "U3") (pin "4") (pinfunction "OB_4") (pintype "passive"))
    )
    (net (code "62") (name "Net-(U5-OA)") (class "Default")
      (node (ref "C19") (pin "2") (pinfunction "2_2") (pintype "passive"))
      (node (ref "M2") (pin "M_A") (pinfunction "M_A_M_A") (pintype "passive"))
      (node (ref "U5") (pin "1") (pinfunction "OA_1") (pintype "passive"))
    )
    (net (code "63") (name "Net-(U5-OB)") (class "Default")
      (node (ref "C19") (pin "1") (pinfunction "1_1") (pintype "passive"))
      (node (ref "M2") (pin "M_B") (pinfunction "M_B_M_B") (pintype "passive"))
      (node (ref "U5") (pin "4") (pinfunction "OB_4") (pintype "passive"))
    )
    (net (code "64") (name "Net-(U6-A)") (class "Default")
      (node (ref "R30") (pin "1") (pinfunction "1_1") (pintype "passive"))
      (node (ref "U6") (pin "1") (pinfunction "A_1") (pintype "passive"))
    )
    (net (code "65") (name "Net-(U7-A)") (class "Default")
      (node (ref "R32") (pin "1") (pinfunction "1_1") (pintype "passive"))
      (node (ref "U7") (pin "1") (pinfunction "A_1") (pintype "passive"))
    )
    (net (code "66") (name "Net-(U8-A)") (class "Default")
      (node (ref "R34") (pin "1") (pinfunction "1_1") (pintype "passive"))
      (node (ref "U8") (pin "1") (pinfunction "A_1") (pintype "passive"))
    )
    (net (code "67") (name "Net-(U9-A)") (class "Default")
      (node (ref "R36") (pin "1") (pinfunction "1_1") (pintype "passive"))
      (node (ref "U9") (pin "1") (pinfunction "A_1") (pintype "passive"))
    )
    (net (code "68") (name "Net-(U10-A)") (class "Default")
      (node (ref "R38") (pin "1") (pinfunction "1_1") (pintype "passive"))
      (node (ref "U10") (pin "1") (pinfunction "A_1") (pintype "passive"))
    )
    (net (code "69") (name "Net-(U11-A)") (class "Default")
      (node (ref "R42") (pin "1") (pinfunction "1_1") (pintype "passive"))
      (node (ref "U11") (pin "1") (pinfunction "A_1") (pintype "passive"))
    )
    (net (code "70") (name "Net-(U12-A)") (class "Default")
      (node (ref "R44") (pin "1") (pinfunction "1_1") (pintype "passive"))
      (node (ref "U12") (pin "1") (pinfunction "A_1") (pintype "passive"))
    )
    (net (code "71") (name "Net-(U13-A)") (class "Default")
      (node (ref "R46") (pin "1") (pinfunction "1_1") (pintype "passive"))
      (node (ref "U13") (pin "1") (pinfunction "A_1") (pintype "passive"))
    )
    (net (code "72") (name "Net-(U14-A)") (class "Default")
      (node (ref "R48") (pin "1") (pinfunction "1_1") (pintype "passive"))
      (node (ref "U14") (pin "1") (pinfunction "A_1") (pintype "passive"))
    )
    (net (code "73") (name "Net-(U15-A)") (class "Default")
      (node (ref "R50") (pin "1") (pinfunction "1_1") (pintype "passive"))
      (node (ref "U15") (pin "1") (pinfunction "A_1") (pintype "passive"))
    )
    (net (code "74") (name "VBUS") (class "Default")
      (node (ref "J1") (pin "A4B9") (pinfunction "VBUS_A4B9") (pintype "power_in"))
      (node (ref "J1") (pin "B4A9") (pinfunction "VBUS_B4A9") (pintype "power_in"))
      (node (ref "R11") (pin "2") (pinfunction "2_2") (pintype "passive"))
      (node (ref "R18") (pin "1") (pinfunction "1_1") (pintype "passive"))
      (node (ref "SW1") (pin "3") (pinfunction "P4_3") (pintype "passive"))
      (node (ref "SW1") (pin "4") (pinfunction "P4_4") (pintype "passive"))
      (node (ref "XH1") (pin "2") (pinfunction "2_2") (pintype "passive"))
    )
    (net (code "75") (name "VDD") (class "Default")
      (node (ref "C9") (pin "2") (pinfunction "2_2") (pintype "passive"))
      (node (ref "R11") (pin "1") (pinfunction "1_1") (pintype "passive"))
      (node (ref "U2") (pin "1") (pinfunction "VDD_1") (pintype "passive"))
    )
    (net (code "76") (name "unconnected-(J1-PadSH)") (class "Default")
      (node (ref "J1") (pin "SH") (pinfunction "SH_SH") (pintype "power_in"))
    )
    (net (code "77") (name "unconnected-(J1-SBU1-PadA8)") (class "Default")
      (node (ref "J1") (pin "A8") (pinfunction "SBU1_A8") (pintype "open_collector+no_connect"))
    )
    (net (code "78") (name "unconnected-(J1-SBU2-PadB8)") (class "Default")
      (node (ref "J1") (pin "B8") (pinfunction "SBU2_B8") (pintype "open_collector+no_connect"))
    )
    (net (code "79") (name "unconnected-(SW1-P1-Pad1)") (class "Default")
      (node (ref "SW1") (pin "1") (pinfunction "P1_1") (pintype "passive+no_connect"))
    )
    (net (code "80") (name "unconnected-(SW1-P1-Pad6)") (class "Default")
      (node (ref "SW1") (pin "6") (pinfunction "P1_6") (pintype "passive+no_connect"))
    )
    (net (code "81") (name "unconnected-(U1A-PB4-Pad40)") (class "Default")
      (node (ref "U1") (pin "40") (pinfunction "PB4_40") (pintype "bidirectional"))
    )
    (net (code "82") (name "unconnected-(U1A-PB5-Pad41)") (class "Default")
      (node (ref "U1") (pin "41") (pinfunction "PB5_41") (pintype "bidirectional"))
    )
    (net (code "83") (name "unconnected-(U1A-PC14-OSC32_IN-Pad3)") (class "Default")
      (node (ref "U1") (pin "3") (pinfunction "PC14-OSC32_IN_3") (pintype "bidirectional+no_connect"))
    )
    (net (code "84") (name "unconnected-(U1A-PC15-OSC32_OUT-Pad4)") (class "Default")
      (node (ref "U1") (pin "4") (pinfunction "PC15-OSC32_OUT_4") (pintype "bidirectional+no_connect"))
    )
    (net (code "85") (name "unconnected-(U1A-PD0-OSC_IN-Pad5)") (class "Default")
      (node (ref "U1") (pin "5") (pinfunction "PD0-OSC_IN_5") (pintype "bidirectional+no_connect"))
    )
    (net (code "86") (name "unconnected-(U1A-PD1-OSC_OUT-Pad6)") (class "Default")
      (node (ref "U1") (pin "6") (pinfunction "PD1-OSC_OUT_6") (pintype "bidirectional+no_connect"))
    )
    (net (code "87") (name "unconnected-(U1B-VBAT-Pad1)") (class "Default")
      (node (ref "U1") (pin "1") (pinfunction "VBAT_1") (pintype "power_in+no_connect"))
    )
    (net (code "88") (name "unconnected-(U2-CFG2-Pad2)") (class "Default")
      (node (ref "U2") (pin "2") (pinfunction "CFG2_2") (pintype "passive"))
    )
    (net (code "89") (name "unconnected-(U2-CFG3-Pad3)") (class "Default")
      (node (ref "U2") (pin "3") (pinfunction "CFG3_3") (pintype "passive"))
    )
    (net (code "90") (name "unconnected-(U4-ADO-Pad7)") (class "Default")
      (node (ref "U4") (pin "7") (pinfunction "ADO_7") (pintype "passive+no_connect"))
    )
    (net (code "91") (name "unconnected-(U4-INT-Pad8)") (class "Default")
      (node (ref "U4") (pin "8") (pinfunction "INT_8") (pintype "passive+no_connect"))
    )
    (net (code "92") (name "unconnected-(U4-XCL-Pad6)") (class "Default")
      (node (ref "U4") (pin "6") (pinfunction "XCL_6") (pintype "passive+no_connect"))
    )
    (net (code "93") (name "unconnected-(U4-XDA-Pad5)") (class "Default")
      (node (ref "U4") (pin "5") (pinfunction "XDA_5") (pintype "passive+no_connect"))
    )
  )
)
